# RawWaves_1-0a.net
KiCad netlist of a schematic drawn in EAGLE
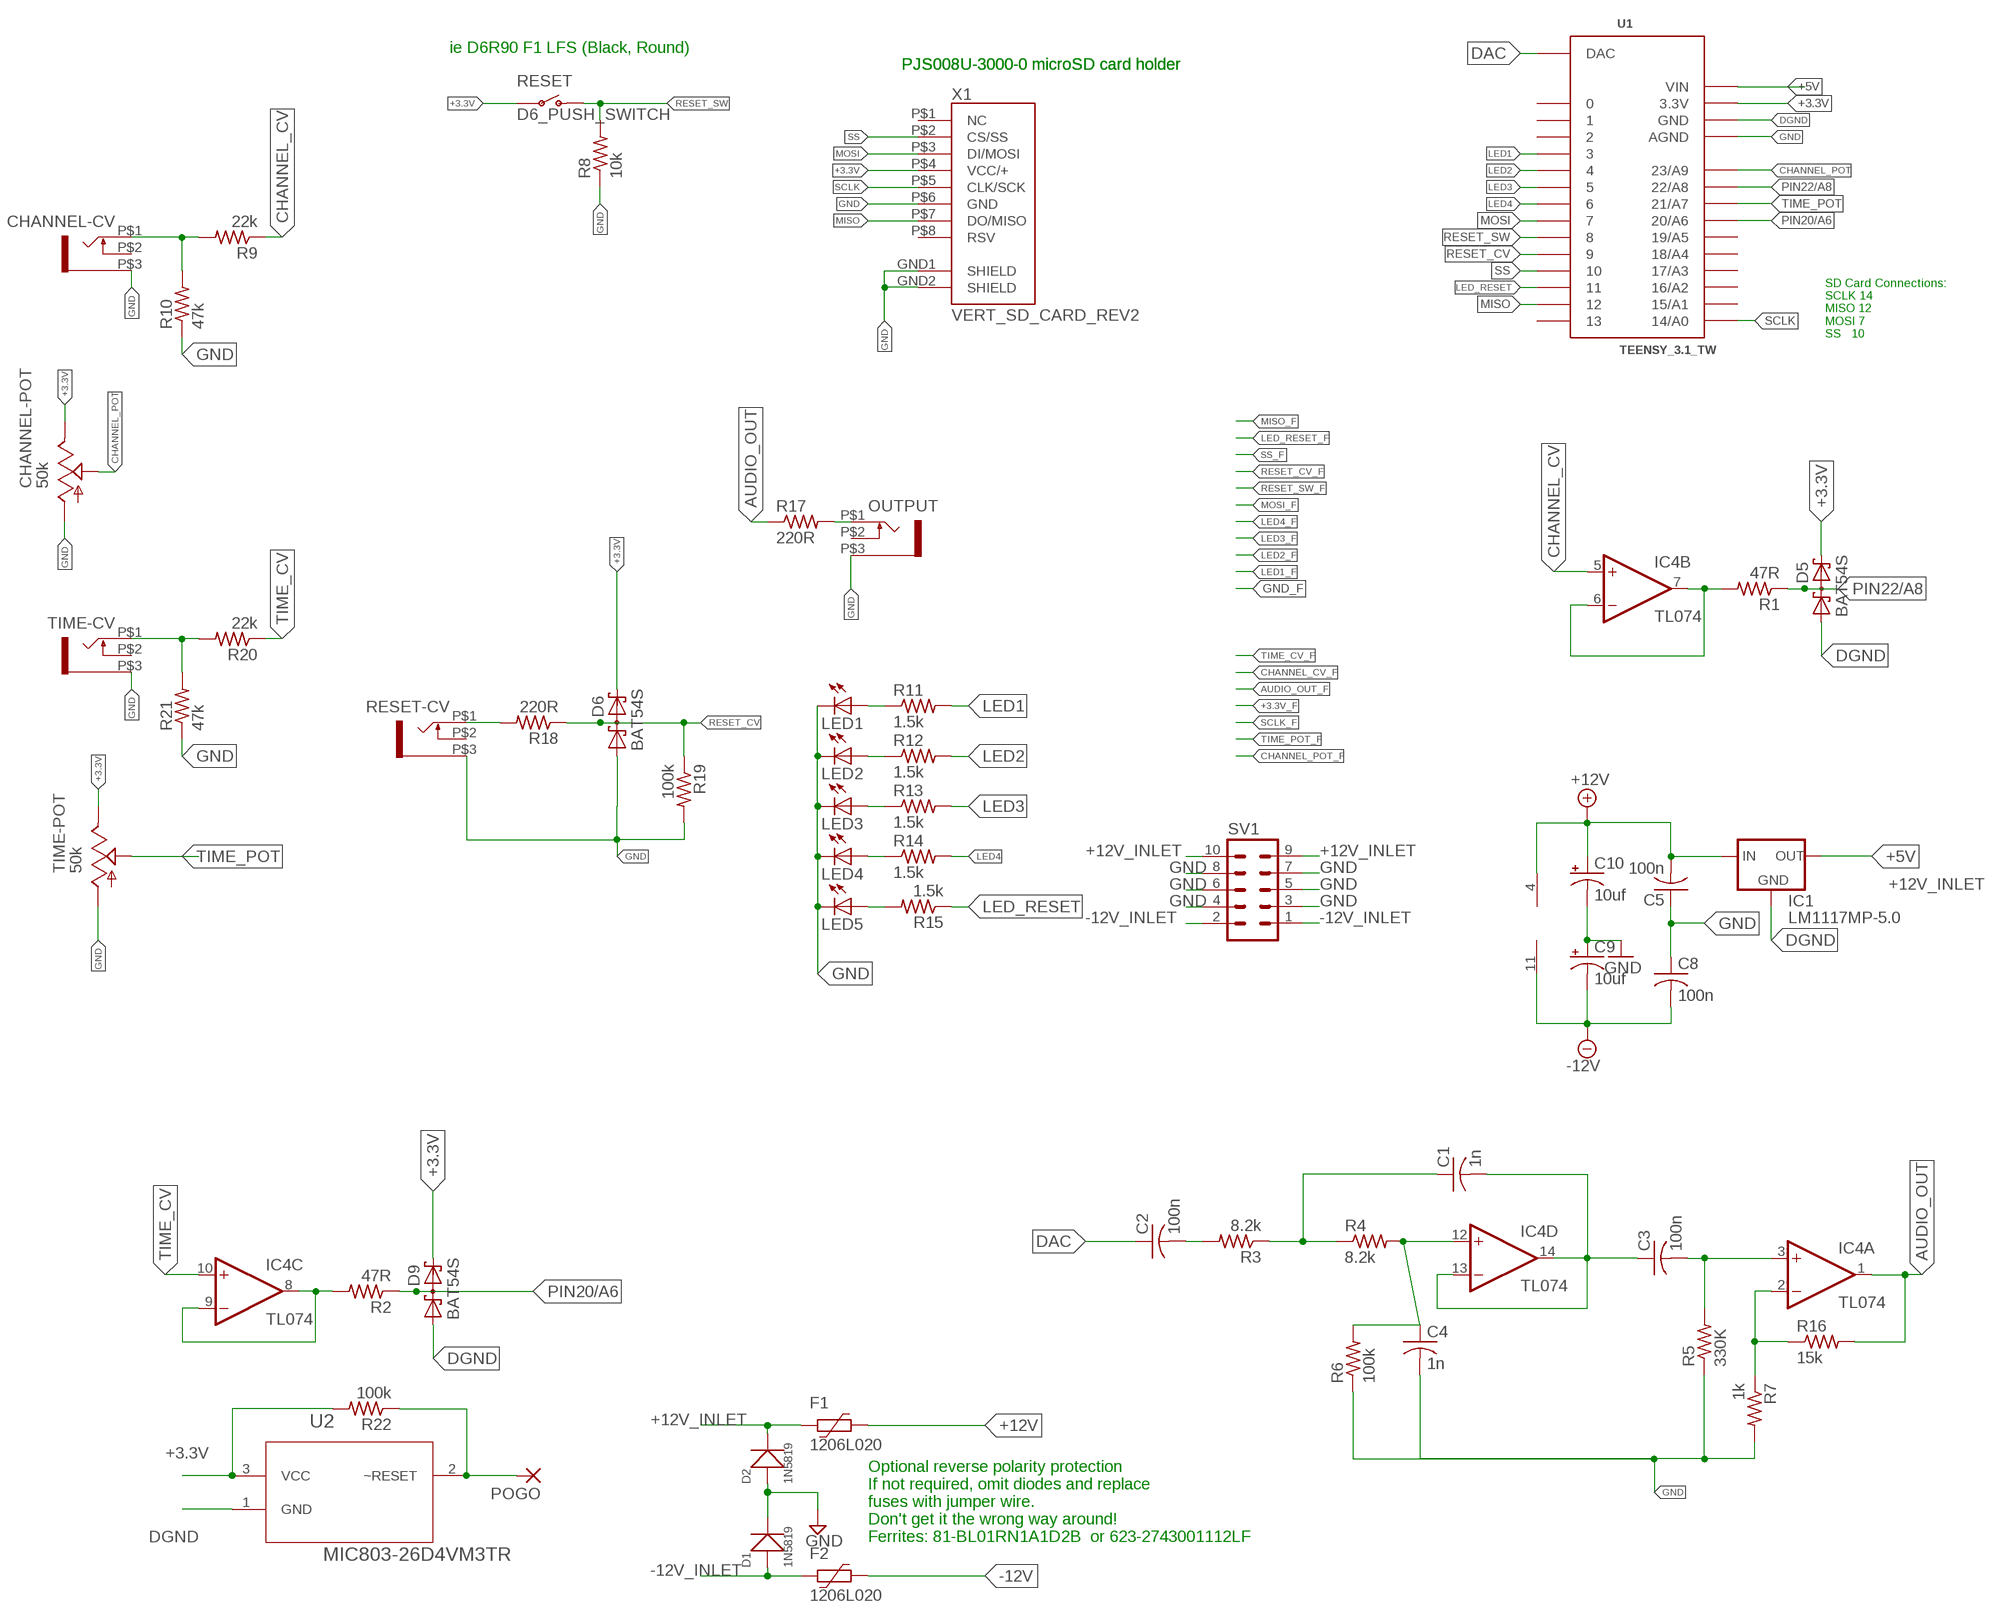
[diagram p0: schematic, sheet 1]

(export (version "E")
  (design (tool "Eeschema 10.0.6"))
  (components
    (comp (ref "C1")
      (value "1n")
      (footprint "eagle-import:C0805")
      (libsource (lib "eagle-import") (part "C-USC0805"))
    )
    (comp (ref "C2")
      (value "100n")
      (footprint "eagle-import:C0805")
      (libsource (lib "eagle-import") (part "C-USC0805"))
    )
    (comp (ref "C3")
      (value "100n")
      (footprint "eagle-import:C0805")
      (libsource (lib "eagle-import") (part "C-USC0805"))
    )
    (comp (ref "C4")
      (value "1n")
      (footprint "eagle-import:C0805")
      (libsource (lib "eagle-import") (part "C-USC0805"))
    )
    (comp (ref "C5")
      (value "100n")
      (footprint "eagle-import:C0805")
      (libsource (lib "eagle-import") (part "C-USC0805"))
    )
    (comp (ref "C8")
      (value "100n")
      (footprint "eagle-import:C0805")
      (libsource (lib "eagle-import") (part "C-USC0805"))
    )
    (comp (ref "C9")
      (value "10uf")
      (footprint "eagle-import:PANASONIC_B")
      (libsource (lib "eagle-import") (part "CPOL-USB"))
    )
    (comp (ref "C10")
      (value "10uf")
      (footprint "eagle-import:PANASONIC_B")
      (libsource (lib "eagle-import") (part "CPOL-USB"))
    )
    (comp (ref "CHANNEL-CV")
      (value "WQP-PJ301M-12_JACK")
      (footprint "eagle-import:WQP-PJ301M-12_JACK")
      (libsource (lib "eagle-import") (part "WQP-PJ301M-12_JACK"))
    )
    (comp (ref "CHANNEL-POT")
      (value "50k")
      (footprint "eagle-import:EVUF")
      (libsource (lib "eagle-import") (part "ALPHA-9MMAF2"))
    )
    (comp (ref "D1")
      (value "1N5819")
      (footprint "eagle-import:SOD-123")
      (fields (field (name "MPN") "B0540W"))
      (libsource (lib "eagle-import") (part "SMD-DIODE-SCHOTTKY-40V-500MA(SOD-123)"))
    )
    (comp (ref "D2")
      (value "1N5819")
      (footprint "eagle-import:SOD-123")
      (fields (field (name "MPN") "B0540W"))
      (libsource (lib "eagle-import") (part "SMD-DIODE-SCHOTTKY-40V-500MA(SOD-123)"))
    )
    (comp (ref "D5")
      (value "BAT54S")
      (footprint "eagle-import:SOT23")
      (libsource (lib "eagle-import") (part "BAT54S"))
    )
    (comp (ref "D6")
      (value "BAT54S")
      (footprint "eagle-import:SOT23")
      (libsource (lib "eagle-import") (part "BAT54S"))
    )
    (comp (ref "D9")
      (value "BAT54S")
      (footprint "eagle-import:SOT23")
      (libsource (lib "eagle-import") (part "BAT54S"))
    )
    (comp (ref "F1")
      (value "1206L020")
      (footprint "eagle-import:1206L")
      (fields (field (name "MF") "Littelfuse"))
      (libsource (lib "eagle-import") (part "?1206L020"))
    )
    (comp (ref "F2")
      (value "1206L020")
      (footprint "eagle-import:1206L")
      (fields (field (name "MF") "Littelfuse"))
      (libsource (lib "eagle-import") (part "?1206L020"))
    )
    (comp (ref "IC1")
      (value "LM1117MP-5.0")
      (footprint "eagle-import:SOT223")
      (fields (field (name "MF") "Texas Instruments"))
      (libsource (lib "eagle-import") (part "LM1117?-MP5.0"))
    )
    (comp (ref "IC4")
      (value "TL074")
      (footprint "eagle-import:SO14")
      (libsource (lib "eagle-import") (part "TL074D"))
    )
    (comp (ref "LED1")
      (value "LED3MM")
      (footprint "eagle-import:LED3MM")
      (libsource (lib "eagle-import") (part "LED3MM"))
    )
    (comp (ref "LED2")
      (value "LED3MM")
      (footprint "eagle-import:LED3MM")
      (libsource (lib "eagle-import") (part "LED3MM"))
    )
    (comp (ref "LED3")
      (value "LED3MM")
      (footprint "eagle-import:LED3MM")
      (libsource (lib "eagle-import") (part "LED3MM"))
    )
    (comp (ref "LED4")
      (value "LED3MM")
      (footprint "eagle-import:LED3MM")
      (libsource (lib "eagle-import") (part "LED3MM"))
    )
    (comp (ref "LED5")
      (value "LED3MM")
      (footprint "eagle-import:LED3MM")
      (libsource (lib "eagle-import") (part "LED3MM"))
    )
    (comp (ref "OUTPUT")
      (value "WQP-PJ301M-12_JACK")
      (footprint "eagle-import:WQP-PJ301M-12_JACK")
      (libsource (lib "eagle-import") (part "WQP-PJ301M-12_JACK"))
    )
    (comp (ref "POGO")
      (value "1,6/0,8")
      (footprint "eagle-import:1,6_0,8")
      (libsource (lib "eagle-import") (part "1,6/0,8"))
    )
    (comp (ref "R1")
      (value "47R")
      (footprint "eagle-import:R0805")
      (libsource (lib "eagle-import") (part "R-US_R0805"))
    )
    (comp (ref "R2")
      (value "47R")
      (footprint "eagle-import:R0805")
      (libsource (lib "eagle-import") (part "R-US_R0805"))
    )
    (comp (ref "R3")
      (value "8.2k")
      (footprint "eagle-import:R0805")
      (libsource (lib "eagle-import") (part "R-US_R0805"))
    )
    (comp (ref "R4")
      (value "8.2k")
      (footprint "eagle-import:R0805")
      (libsource (lib "eagle-import") (part "R-US_R0805"))
    )
    (comp (ref "R5")
      (value "330K")
      (footprint "eagle-import:R0805")
      (libsource (lib "eagle-import") (part "R-US_R0805"))
    )
    (comp (ref "R6")
      (value "100k")
      (footprint "eagle-import:R0805")
      (libsource (lib "eagle-import") (part "R-US_R0805"))
    )
    (comp (ref "R7")
      (value "1k")
      (footprint "eagle-import:R0805")
      (libsource (lib "eagle-import") (part "R-US_R0805"))
    )
    (comp (ref "R8")
      (value "10k")
      (footprint "eagle-import:R0805")
      (libsource (lib "eagle-import") (part "R-US_R0805"))
    )
    (comp (ref "R9")
      (value "22k")
      (footprint "eagle-import:R0805")
      (libsource (lib "eagle-import") (part "R-US_R0805"))
    )
    (comp (ref "R10")
      (value "47k")
      (footprint "eagle-import:R0805")
      (libsource (lib "eagle-import") (part "R-US_R0805"))
    )
    (comp (ref "R11")
      (value "1.5k")
      (footprint "eagle-import:R0805")
      (libsource (lib "eagle-import") (part "R-US_R0805"))
    )
    (comp (ref "R12")
      (value "1.5k")
      (footprint "eagle-import:R0805")
      (libsource (lib "eagle-import") (part "R-US_R0805"))
    )
    (comp (ref "R13")
      (value "1.5k")
      (footprint "eagle-import:R0805")
      (libsource (lib "eagle-import") (part "R-US_R0805"))
    )
    (comp (ref "R14")
      (value "1.5k")
      (footprint "eagle-import:R0805")
      (libsource (lib "eagle-import") (part "R-US_R0805"))
    )
    (comp (ref "R15")
      (value "1.5k")
      (footprint "eagle-import:R0805")
      (libsource (lib "eagle-import") (part "R-US_R0805"))
    )
    (comp (ref "R16")
      (value "15k")
      (footprint "eagle-import:R0805")
      (libsource (lib "eagle-import") (part "R-US_R0805"))
    )
    (comp (ref "R17")
      (value "220R")
      (footprint "eagle-import:R0805")
      (libsource (lib "eagle-import") (part "R-US_R0805"))
    )
    (comp (ref "R18")
      (value "220R")
      (footprint "eagle-import:R0805")
      (libsource (lib "eagle-import") (part "R-US_R0805"))
    )
    (comp (ref "R19")
      (value "100k")
      (footprint "eagle-import:R0805")
      (libsource (lib "eagle-import") (part "R-US_R0805"))
    )
    (comp (ref "R20")
      (value "22k")
      (footprint "eagle-import:R0805")
      (libsource (lib "eagle-import") (part "R-US_R0805"))
    )
    (comp (ref "R21")
      (value "47k")
      (footprint "eagle-import:R0805")
      (libsource (lib "eagle-import") (part "R-US_R0805"))
    )
    (comp (ref "R22")
      (value "100k")
      (footprint "eagle-import:R0805")
      (libsource (lib "eagle-import") (part "R-US_R0805"))
    )
    (comp (ref "RESET")
      (value "D6_PUSH_SWITCH")
      (footprint "eagle-import:D6_BUTTON_RND")
      (libsource (lib "eagle-import") (part "D6_PUSH_SWITCH"))
    )
    (comp (ref "RESET-CV")
      (value "WQP-PJ301M-12_JACK")
      (footprint "eagle-import:WQP-PJ301M-12_JACK")
      (libsource (lib "eagle-import") (part "WQP-PJ301M-12_JACK"))
    )
    (comp (ref "SV1")
      (value "10_PIN_HEADER")
      (footprint "eagle-import:MA05-2")
      (libsource (lib "eagle-import") (part "10_PIN_HEADER"))
    )
    (comp (ref "TIME-CV")
      (value "WQP-PJ301M-12_JACK")
      (footprint "eagle-import:WQP-PJ301M-12_JACK")
      (libsource (lib "eagle-import") (part "WQP-PJ301M-12_JACK"))
    )
    (comp (ref "TIME-POT")
      (value "50k")
      (footprint "eagle-import:EVUF")
      (libsource (lib "eagle-import") (part "ALPHA-9MMAF2"))
    )
    (comp (ref "U1")
      (value "TEENSY_3.1_TW")
      (footprint "eagle-import:TEENSY_3.1_TW")
      (libsource (lib "eagle-import") (part "TEENSY_3.1_TW"))
    )
    (comp (ref "U2")
      (value "MIC803-26D4VM3TR")
      (footprint "eagle-import:SOT95P232X110-3N")
      (libsource (lib "eagle-import") (part "MIC803-26D4VM3TR"))
    )
    (comp (ref "X1")
      (value "VERT_SD_CARD_REV2")
      (footprint "eagle-import:VERT_MICROSD_REV2")
      (libsource (lib "eagle-import") (part "VERT_SD_CARD_REV2"))
    )
  )
  (nets
    (net (code "1") (name "+3.3V") (class "Default")
      (node (ref "CHANNEL-POT") (pin "3") (pinfunction "E_3") (pintype "passive"))
      (node (ref "D5") (pin "2") (pinfunction "C2_2") (pintype "passive"))
      (node (ref "D6") (pin "2") (pinfunction "C2_2") (pintype "passive"))
      (node (ref "D9") (pin "2") (pinfunction "C2_2") (pintype "passive"))
      (node (ref "R22") (pin "2") (pinfunction "2_2") (pintype "passive"))
      (node (ref "RESET") (pin "P$3") (pinfunction "P_P$3") (pintype "passive"))
      (node (ref "RESET") (pin "P$4") (pinfunction "P_P$4") (pintype "passive"))
      (node (ref "TIME-POT") (pin "3") (pinfunction "E_3") (pintype "passive"))
      (node (ref "U1") (pin "3.3V") (pinfunction "3.3V_3.3V") (pintype "power_in"))
      (node (ref "U2") (pin "3") (pinfunction "VCC_3") (pintype "power_in"))
      (node (ref "X1") (pin "P$4") (pinfunction "VCC/+_P$4") (pintype "bidirectional"))
    )
    (net (code "3") (name "+5V") (class "Default")
      (node (ref "IC1") (pin "2") (pinfunction "OUT_2") (pintype "passive"))
      (node (ref "IC1") (pin "4") (pinfunction "OUT_4") (pintype "passive"))
      (node (ref "U1") (pin "VIN") (pinfunction "VIN_VIN") (pintype "power_in"))
    )
    (net (code "4") (name "+12V") (class "Default")
      (node (ref "C10") (pin "+") (pinfunction "+_+") (pintype "passive"))
      (node (ref "C5") (pin "2") (pinfunction "2_2") (pintype "passive"))
      (node (ref "F1") (pin "1") (pinfunction "1_1") (pintype "passive"))
      (node (ref "IC1") (pin "3") (pinfunction "IN_3") (pintype "input"))
      (node (ref "IC4") (pin "4") (pinfunction "V+_4") (pintype "power_in"))
    )
    (net (code "5") (name "-12V") (class "Default")
      (node (ref "C8") (pin "2") (pinfunction "2_2") (pintype "passive"))
      (node (ref "C9") (pin "-") (pinfunction "-_-") (pintype "passive"))
      (node (ref "F2") (pin "1") (pinfunction "1_1") (pintype "passive"))
      (node (ref "IC4") (pin "11") (pinfunction "V-_11") (pintype "power_in"))
    )
    (net (code "6") (name "/+12V_INLET") (class "Default")
      (node (ref "D2") (pin "-") (pinfunction "-_-") (pintype "passive"))
      (node (ref "F1") (pin "2") (pinfunction "2_2") (pintype "passive"))
      (node (ref "SV1") (pin "10") (pinfunction "10_10") (pintype "passive"))
      (node (ref "SV1") (pin "9") (pinfunction "9_9") (pintype "passive"))
    )
    (net (code "7") (name "/-12V_INLET") (class "Default")
      (node (ref "D1") (pin "+") (pinfunction "+_+") (pintype "passive"))
      (node (ref "F2") (pin "2") (pinfunction "2_2") (pintype "passive"))
      (node (ref "SV1") (pin "1") (pinfunction "1_1") (pintype "passive"))
      (node (ref "SV1") (pin "2") (pinfunction "2_2") (pintype "passive"))
    )
    (net (code "8") (name "AUDIO_OUT") (class "Default")
      (node (ref "IC4") (pin "1") (pinfunction "OUT_1") (pintype "output"))
      (node (ref "R16") (pin "2") (pinfunction "2_2") (pintype "passive"))
      (node (ref "R17") (pin "1") (pinfunction "1_1") (pintype "passive"))
    )
    (net (code "10") (name "CHANNEL_CV") (class "Default")
      (node (ref "IC4") (pin "5") (pinfunction "+IN_5") (pintype "input"))
      (node (ref "R9") (pin "1") (pinfunction "1_1") (pintype "passive"))
    )
    (net (code "12") (name "CHANNEL_POT") (class "Default")
      (node (ref "CHANNEL-POT") (pin "2") (pinfunction "S_2") (pintype "passive"))
      (node (ref "U1") (pin "23/A9") (pinfunction "23/A9_23/A9") (pintype "bidirectional"))
    )
    (net (code "14") (name "DAC") (class "Default")
      (node (ref "C2") (pin "1") (pinfunction "1_1") (pintype "passive"))
      (node (ref "U1") (pin "DAC") (pinfunction "DAC_DAC") (pintype "bidirectional"))
    )
    (net (code "15") (name "DGND") (class "Default")
      (node (ref "D5") (pin "1") (pinfunction "A1_1") (pintype "passive"))
      (node (ref "D9") (pin "1") (pinfunction "A1_1") (pintype "passive"))
      (node (ref "IC1") (pin "1") (pinfunction "GND_1") (pintype "input"))
      (node (ref "U1") (pin "GND") (pinfunction "GND_GND") (pintype "power_in"))
      (node (ref "U2") (pin "1") (pinfunction "GND_1") (pintype "passive"))
    )
    (net (code "16") (name "GND") (class "Default")
      (node (ref "C10") (pin "-") (pinfunction "-_-") (pintype "passive"))
      (node (ref "C4") (pin "2") (pinfunction "2_2") (pintype "passive"))
      (node (ref "C5") (pin "1") (pinfunction "1_1") (pintype "passive"))
      (node (ref "C8") (pin "1") (pinfunction "1_1") (pintype "passive"))
      (node (ref "C9") (pin "+") (pinfunction "+_+") (pintype "passive"))
      (node (ref "CHANNEL-CV") (pin "P$3") (pinfunction "1_P$3") (pintype "passive"))
      (node (ref "CHANNEL-POT") (pin "1") (pinfunction "A_1") (pintype "passive"))
      (node (ref "D1") (pin "-") (pinfunction "-_-") (pintype "passive"))
      (node (ref "D2") (pin "+") (pinfunction "+_+") (pintype "passive"))
      (node (ref "D6") (pin "1") (pinfunction "A1_1") (pintype "passive"))
      (node (ref "LED1") (pin "K") (pinfunction "C_K") (pintype "passive"))
      (node (ref "LED2") (pin "K") (pinfunction "C_K") (pintype "passive"))
      (node (ref "LED3") (pin "K") (pinfunction "C_K") (pintype "passive"))
      (node (ref "LED4") (pin "K") (pinfunction "C_K") (pintype "passive"))
      (node (ref "LED5") (pin "K") (pinfunction "C_K") (pintype "passive"))
      (node (ref "OUTPUT") (pin "P$3") (pinfunction "1_P$3") (pintype "passive"))
      (node (ref "R10") (pin "1") (pinfunction "1_1") (pintype "passive"))
      (node (ref "R19") (pin "2") (pinfunction "2_2") (pintype "passive"))
      (node (ref "R21") (pin "1") (pinfunction "1_1") (pintype "passive"))
      (node (ref "R5") (pin "1") (pinfunction "1_1") (pintype "passive"))
      (node (ref "R6") (pin "1") (pinfunction "1_1") (pintype "passive"))
      (node (ref "R7") (pin "2") (pinfunction "2_2") (pintype "passive"))
      (node (ref "R8") (pin "1") (pinfunction "1_1") (pintype "passive"))
      (node (ref "RESET-CV") (pin "P$3") (pinfunction "1_P$3") (pintype "passive"))
      (node (ref "SV1") (pin "3") (pinfunction "3_3") (pintype "passive"))
      (node (ref "SV1") (pin "4") (pinfunction "4_4") (pintype "passive"))
      (node (ref "SV1") (pin "5") (pinfunction "5_5") (pintype "passive"))
      (node (ref "SV1") (pin "6") (pinfunction "6_6") (pintype "passive"))
      (node (ref "SV1") (pin "7") (pinfunction "7_7") (pintype "passive"))
      (node (ref "SV1") (pin "8") (pinfunction "8_8") (pintype "passive"))
      (node (ref "TIME-CV") (pin "P$3") (pinfunction "1_P$3") (pintype "passive"))
      (node (ref "TIME-POT") (pin "1") (pinfunction "A_1") (pintype "passive"))
      (node (ref "U1") (pin "AGND") (pinfunction "AGND_AGND") (pintype "power_in"))
      (node (ref "X1") (pin "GND1") (pinfunction "SHIELD_GND1") (pintype "bidirectional"))
      (node (ref "X1") (pin "GND2") (pinfunction "SHIELD_GND2") (pintype "bidirectional"))
      (node (ref "X1") (pin "P$6") (pinfunction "GND_P$6") (pintype "bidirectional"))
    )
    (net (code "18") (name "LED1") (class "Default")
      (node (ref "R11") (pin "2") (pinfunction "2_2") (pintype "passive"))
      (node (ref "U1") (pin "3") (pinfunction "3_3") (pintype "bidirectional"))
    )
    (net (code "20") (name "LED2") (class "Default")
      (node (ref "R12") (pin "2") (pinfunction "2_2") (pintype "passive"))
      (node (ref "U1") (pin "4") (pinfunction "4_4") (pintype "bidirectional"))
    )
    (net (code "22") (name "LED3") (class "Default")
      (node (ref "R13") (pin "2") (pinfunction "2_2") (pintype "passive"))
      (node (ref "U1") (pin "5") (pinfunction "5_5") (pintype "bidirectional"))
    )
    (net (code "24") (name "LED4") (class "Default")
      (node (ref "R14") (pin "2") (pinfunction "2_2") (pintype "passive"))
      (node (ref "U1") (pin "6") (pinfunction "6_6") (pintype "bidirectional"))
    )
    (net (code "26") (name "LED_RESET") (class "Default")
      (node (ref "R15") (pin "1") (pinfunction "1_1") (pintype "passive"))
      (node (ref "U1") (pin "11") (pinfunction "11_11") (pintype "bidirectional"))
    )
    (net (code "28") (name "MISO") (class "Default")
      (node (ref "U1") (pin "12") (pinfunction "12_12") (pintype "bidirectional"))
      (node (ref "X1") (pin "P$7") (pinfunction "DO/MISO_P$7") (pintype "bidirectional"))
    )
    (net (code "30") (name "MOSI") (class "Default")
      (node (ref "U1") (pin "7") (pinfunction "7_7") (pintype "bidirectional"))
      (node (ref "X1") (pin "P$3") (pinfunction "DI/MOSI_P$3") (pintype "bidirectional"))
    )
    (net (code "32") (name "Net-(C1-Pad1)") (class "Default")
      (node (ref "C1") (pin "1") (pinfunction "1_1") (pintype "passive"))
      (node (ref "R3") (pin "1") (pinfunction "1_1") (pintype "passive"))
      (node (ref "R4") (pin "1") (pinfunction "1_1") (pintype "passive"))
    )
    (net (code "33") (name "Net-(C2-Pad2)") (class "Default")
      (node (ref "C2") (pin "2") (pinfunction "2_2") (pintype "passive"))
      (node (ref "R3") (pin "2") (pinfunction "2_2") (pintype "passive"))
    )
    (net (code "34") (name "Net-(CHANNEL-CV-2)") (class "Default")
      (node (ref "CHANNEL-CV") (pin "P$1") (pinfunction "2_P$1") (pintype "passive"))
      (node (ref "R10") (pin "2") (pinfunction "2_2") (pintype "passive"))
      (node (ref "R9") (pin "2") (pinfunction "2_2") (pintype "passive"))
    )
    (net (code "35") (name "Net-(IC4A-+IN)") (class "Default")
      (node (ref "C3") (pin "2") (pinfunction "2_2") (pintype "passive"))
      (node (ref "IC4") (pin "3") (pinfunction "+IN_3") (pintype "input"))
      (node (ref "R5") (pin "2") (pinfunction "2_2") (pintype "passive"))
    )
    (net (code "36") (name "Net-(IC4A--IN)") (class "Default")
      (node (ref "IC4") (pin "2") (pinfunction "-IN_2") (pintype "input"))
      (node (ref "R16") (pin "1") (pinfunction "1_1") (pintype "passive"))
      (node (ref "R7") (pin "1") (pinfunction "1_1") (pintype "passive"))
    )
    (net (code "37") (name "Net-(IC4B--IN)") (class "Default")
      (node (ref "IC4") (pin "6") (pinfunction "-IN_6") (pintype "input"))
      (node (ref "IC4") (pin "7") (pinfunction "OUT_7") (pintype "output"))
      (node (ref "R1") (pin "2") (pinfunction "2_2") (pintype "passive"))
    )
    (net (code "38") (name "Net-(IC4C--IN)") (class "Default")
      (node (ref "IC4") (pin "8") (pinfunction "OUT_8") (pintype "output"))
      (node (ref "IC4") (pin "9") (pinfunction "-IN_9") (pintype "input"))
      (node (ref "R2") (pin "2") (pinfunction "2_2") (pintype "passive"))
    )
    (net (code "39") (name "Net-(IC4D-+IN)") (class "Default")
      (node (ref "C4") (pin "1") (pinfunction "1_1") (pintype "passive"))
      (node (ref "IC4") (pin "12") (pinfunction "+IN_12") (pintype "input"))
      (node (ref "R4") (pin "2") (pinfunction "2_2") (pintype "passive"))
      (node (ref "R6") (pin "2") (pinfunction "2_2") (pintype "passive"))
    )
    (net (code "40") (name "Net-(IC4D--IN)") (class "Default")
      (node (ref "C1") (pin "2") (pinfunction "2_2") (pintype "passive"))
      (node (ref "C3") (pin "1") (pinfunction "1_1") (pintype "passive"))
      (node (ref "IC4") (pin "13") (pinfunction "-IN_13") (pintype "input"))
      (node (ref "IC4") (pin "14") (pinfunction "OUT_14") (pintype "output"))
    )
    (net (code "41") (name "Net-(LED1-PadA)") (class "Default")
      (node (ref "LED1") (pin "A") (pinfunction "A_A") (pintype "passive"))
      (node (ref "R11") (pin "1") (pinfunction "1_1") (pintype "passive"))
    )
    (net (code "42") (name "Net-(LED2-PadA)") (class "Default")
      (node (ref "LED2") (pin "A") (pinfunction "A_A") (pintype "passive"))
      (node (ref "R12") (pin "1") (pinfunction "1_1") (pintype "passive"))
    )
    (net (code "43") (name "Net-(LED3-PadA)") (class "Default")
      (node (ref "LED3") (pin "A") (pinfunction "A_A") (pintype "passive"))
      (node (ref "R13") (pin "1") (pinfunction "1_1") (pintype "passive"))
    )
    (net (code "44") (name "Net-(LED4-PadA)") (class "Default")
      (node (ref "LED4") (pin "A") (pinfunction "A_A") (pintype "passive"))
      (node (ref "R14") (pin "1") (pinfunction "1_1") (pintype "passive"))
    )
    (net (code "45") (name "Net-(LED5-PadA)") (class "Default")
      (node (ref "LED5") (pin "A") (pinfunction "A_A") (pintype "passive"))
      (node (ref "R15") (pin "2") (pinfunction "2_2") (pintype "passive"))
    )
    (net (code "46") (name "Net-(OUTPUT-2)") (class "Default")
      (node (ref "OUTPUT") (pin "P$1") (pinfunction "2_P$1") (pintype "passive"))
      (node (ref "R17") (pin "2") (pinfunction "2_2") (pintype "passive"))
    )
    (net (code "47") (name "Net-(POGO-P)") (class "Default")
      (node (ref "POGO") (pin "1") (pinfunction "P_1") (pintype "passive"))
      (node (ref "R22") (pin "1") (pinfunction "1_1") (pintype "passive"))
      (node (ref "U2") (pin "2") (pinfunction "~{RESET}_2") (pintype "passive"))
    )
    (net (code "48") (name "Net-(RESET-CV-2)") (class "Default")
      (node (ref "R18") (pin "2") (pinfunction "2_2") (pintype "passive"))
      (node (ref "RESET-CV") (pin "P$1") (pinfunction "2_P$1") (pintype "passive"))
    )
    (net (code "49") (name "Net-(TIME-CV-2)") (class "Default")
      (node (ref "R20") (pin "2") (pinfunction "2_2") (pintype "passive"))
      (node (ref "R21") (pin "2") (pinfunction "2_2") (pintype "passive"))
      (node (ref "TIME-CV") (pin "P$1") (pinfunction "2_P$1") (pintype "passive"))
    )
    (net (code "50") (name "PIN20{slash}A6") (class "Default")
      (node (ref "D9") (pin "3") (pinfunction "C1A2_3") (pintype "passive"))
      (node (ref "R2") (pin "1") (pinfunction "1_1") (pintype "passive"))
      (node (ref "U1") (pin "20/A6") (pinfunction "20/A6_20/A6") (pintype "bidirectional"))
    )
    (net (code "51") (name "PIN22{slash}A8") (class "Default")
      (node (ref "D5") (pin "3") (pinfunction "C1A2_3") (pintype "passive"))
      (node (ref "R1") (pin "1") (pinfunction "1_1") (pintype "passive"))
      (node (ref "U1") (pin "22/A8") (pinfunction "22/A8_22/A8") (pintype "bidirectional"))
    )
    (net (code "52") (name "RESET_CV") (class "Default")
      (node (ref "D6") (pin "3") (pinfunction "C1A2_3") (pintype "passive"))
      (node (ref "R18") (pin "1") (pinfunction "1_1") (pintype "passive"))
      (node (ref "R19") (pin "1") (pinfunction "1_1") (pintype "passive"))
      (node (ref "U1") (pin "9") (pinfunction "9_9") (pintype "bidirectional"))
    )
    (net (code "54") (name "RESET_SW") (class "Default")
      (node (ref "R8") (pin "2") (pinfunction "2_2") (pintype "passive"))
      (node (ref "RESET") (pin "P$1") (pinfunction "O_P$1") (pintype "passive"))
      (node (ref "RESET") (pin "P$2") (pinfunction "O_P$2") (pintype "passive"))
      (node (ref "U1") (pin "8") (pinfunction "8_8") (pintype "bidirectional"))
    )
    (net (code "56") (name "SCLK") (class "Default")
      (node (ref "U1") (pin "14/A0") (pinfunction "14/A0_14/A0") (pintype "bidirectional"))
      (node (ref "X1") (pin "P$5") (pinfunction "CLK/SCK_P$5") (pintype "bidirectional"))
    )
    (net (code "58") (name "SS") (class "Default")
      (node (ref "U1") (pin "10") (pinfunction "10_10") (pintype "bidirectional"))
      (node (ref "X1") (pin "P$2") (pinfunction "CS/SS_P$2") (pintype "bidirectional"))
    )
    (net (code "60") (name "TIME_CV") (class "Default")
      (node (ref "IC4") (pin "10") (pinfunction "+IN_10") (pintype "input"))
      (node (ref "R20") (pin "1") (pinfunction "1_1") (pintype "passive"))
    )
    (net (code "62") (name "TIME_POT") (class "Default")
      (node (ref "TIME-POT") (pin "2") (pinfunction "S_2") (pintype "passive"))
      (node (ref "U1") (pin "21/A7") (pinfunction "21/A7_21/A7") (pintype "bidirectional"))
    )
    (net (code "64") (name "unconnected-(CHANNEL-CV-3-PadP$2)") (class "Default")
      (node (ref "CHANNEL-CV") (pin "P$2") (pinfunction "3_P$2") (pintype "passive"))
    )
    (net (code "65") (name "unconnected-(OUTPUT-3-PadP$2)") (class "Default")
      (node (ref "OUTPUT") (pin "P$2") (pinfunction "3_P$2") (pintype "passive"))
    )
    (net (code "66") (name "unconnected-(RESET-CV-3-PadP$2)") (class "Default")
      (node (ref "RESET-CV") (pin "P$2") (pinfunction "3_P$2") (pintype "passive"))
    )
    (net (code "67") (name "unconnected-(TIME-CV-3-PadP$2)") (class "Default")
      (node (ref "TIME-CV") (pin "P$2") (pinfunction "3_P$2") (pintype "passive"))
    )
    (net (code "68") (name "unconnected-(U1-Pad0)") (class "Default")
      (node (ref "U1") (pin "0") (pinfunction "0_0") (pintype "bidirectional"))
    )
    (net (code "69") (name "unconnected-(U1-Pad1)") (class "Default")
      (node (ref "U1") (pin "1") (pinfunction "1_1") (pintype "bidirectional"))
    )
    (net (code "70") (name "unconnected-(U1-Pad2)") (class "Default")
      (node (ref "U1") (pin "2") (pinfunction "2_2") (pintype "bidirectional"))
    )
    (net (code "71") (name "unconnected-(U1-Pad13)") (class "Default")
      (node (ref "U1") (pin "13") (pinfunction "13_13") (pintype "bidirectional"))
    )
    (net (code "72") (name "unconnected-(U1-Pad15{slash}A1)") (class "Default")
      (node (ref "U1") (pin "15/A1") (pinfunction "15/A1_15/A1") (pintype "bidirectional"))
    )
    (net (code "73") (name "unconnected-(U1-Pad16{slash}A2)") (class "Default")
      (node (ref "U1") (pin "16/A2") (pinfunction "16/A2_16/A2") (pintype "bidirectional"))
    )
    (net (code "74") (name "unconnected-(U1-Pad17{slash}A3)") (class "Default")
      (node (ref "U1") (pin "17/A3") (pinfunction "17/A3_17/A3") (pintype "bidirectional"))
    )
    (net (code "75") (name "unconnected-(U1-Pad18{slash}A4)") (class "Default")
      (node (ref "U1") (pin "18/A4") (pinfunction "18/A4_18/A4") (pintype "bidirectional"))
    )
    (net (code "76") (name "unconnected-(U1-Pad19{slash}A5)") (class "Default")
      (node (ref "U1") (pin "19/A5") (pinfunction "19/A5_19/A5") (pintype "bidirectional"))
    )
    (net (code "77") (name "unconnected-(X1-NC-PadP$1)") (class "Default")
      (node (ref "X1") (pin "P$1") (pinfunction "NC_P$1") (pintype "bidirectional"))
    )
    (net (code "78") (name "unconnected-(X1-RSV-PadP$8)") (class "Default")
      (node (ref "X1") (pin "P$8") (pinfunction "RSV_P$8") (pintype "bidirectional"))
    )
  )
)
